# Grove_-_NFC_Tag_v1_0.net
KiCad netlist of a schematic drawn in EAGLE
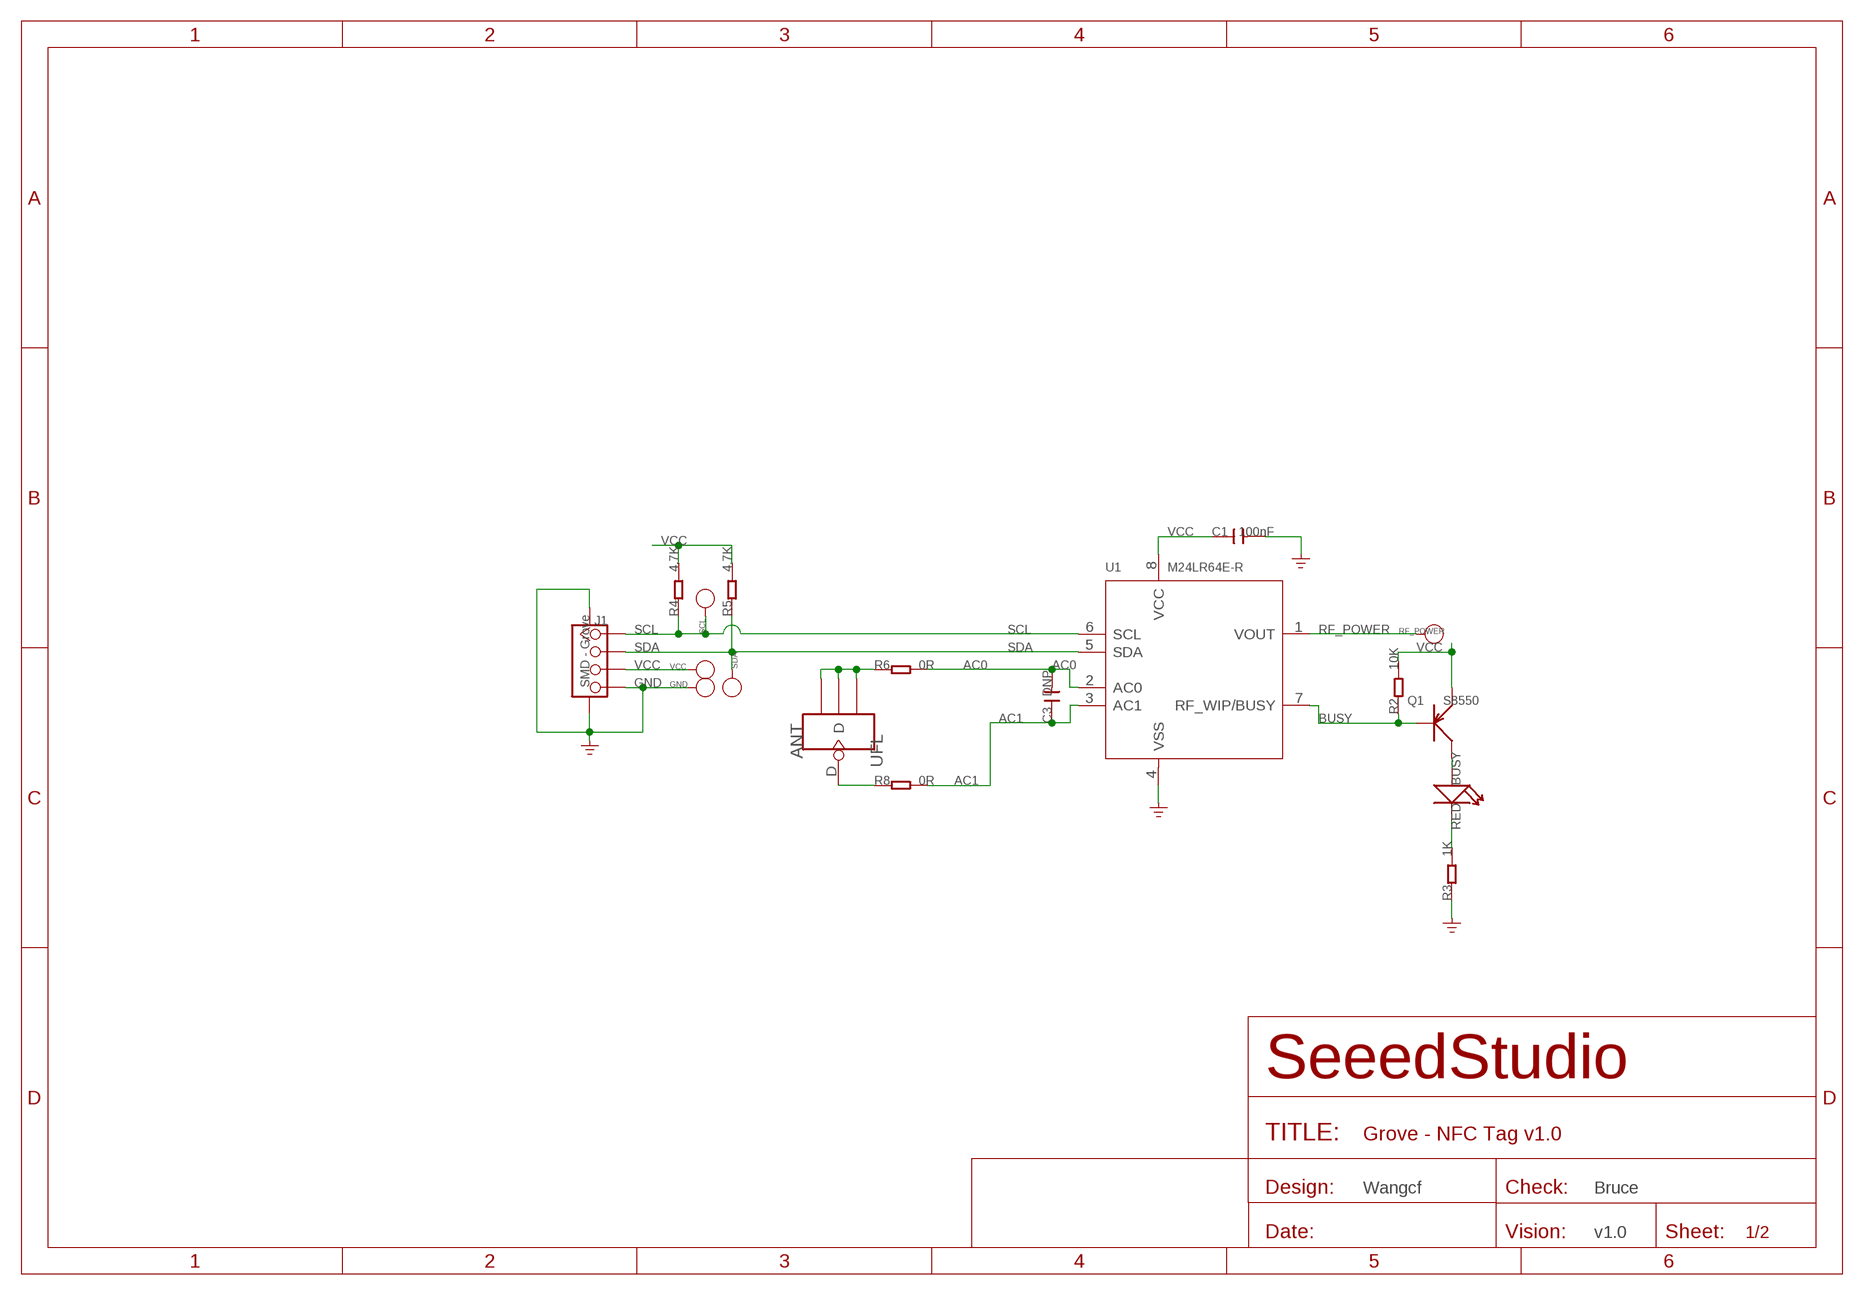
[diagram p0: schematic, sheet 1]
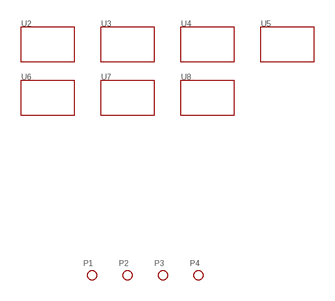
[diagram p1: schematic, sheet 2]

(export (version "E")
  (design (tool "Eeschema 10.0.6"))
  (components
    (comp (ref "ANT")
      (value "UFL")
      (footprint "eagle-import:4P-U-FL")
      (libsource (lib "eagle-import") (part "ANTENNA-U-FL"))
    )
    (comp (ref "BUSY")
      (value "RED")
      (footprint "eagle-import:LED-0603")
      (libsource (lib "eagle-import") (part "LED'0603'"))
    )
    (comp (ref "C1")
      (value "100nF")
      (footprint "eagle-import:C0402")
      (libsource (lib "eagle-import") (part "C-0402"))
    )
    (comp (ref "C3")
      (value "DNP")
      (footprint "eagle-import:C0402")
      (libsource (lib "eagle-import") (part "C-0402"))
    )
    (comp (ref "GND")
      (value "PAD-TEST-POINT'4545'")
      (footprint "eagle-import:TP_4545")
      (fields (field (name "PARTNO") "DNP"))
      (libsource (lib "eagle-import") (part "PAD-TEST-POINT'4545'"))
    )
    (comp (ref "J1")
      (value "SMD - Grove")
      (footprint "eagle-import:4P-SMD-2.0")
      (libsource (lib "eagle-import") (part "TWIG-4P-2.0-SMD-FEMALE-REINFORCE'DD'"))
    )
    (comp (ref "Q1")
      (value "S8550")
      (footprint "eagle-import:SOT23")
      (libsource (lib "eagle-import") (part "TRANSISTOR-PNP-SOT23"))
    )
    (comp (ref "R2")
      (value "10K")
      (footprint "eagle-import:R0402")
      (libsource (lib "eagle-import") (part "R-0402"))
    )
    (comp (ref "R3")
      (value "1K")
      (footprint "eagle-import:R0402")
      (libsource (lib "eagle-import") (part "R-0402"))
    )
    (comp (ref "R4")
      (value "4.7K")
      (footprint "eagle-import:R0402")
      (libsource (lib "eagle-import") (part "R-0402"))
    )
    (comp (ref "R5")
      (value "4.7K")
      (footprint "eagle-import:R0402")
      (libsource (lib "eagle-import") (part "R-0402"))
    )
    (comp (ref "R6")
      (value "0R")
      (footprint "eagle-import:R0402")
      (libsource (lib "eagle-import") (part "R-0402"))
    )
    (comp (ref "R8")
      (value "0R")
      (footprint "eagle-import:R0402")
      (libsource (lib "eagle-import") (part "R-0402"))
    )
    (comp (ref "RF_POWER")
      (value "PAD-TEST-POINT'4545'")
      (footprint "eagle-import:TP_4545")
      (fields (field (name "PARTNO") "DNP"))
      (libsource (lib "eagle-import") (part "PAD-TEST-POINT'4545'"))
    )
    (comp (ref "SCL")
      (value "PAD-TEST-POINT'4545'")
      (footprint "eagle-import:TP_4545")
      (fields (field (name "PARTNO") "DNP"))
      (libsource (lib "eagle-import") (part "PAD-TEST-POINT'4545'"))
    )
    (comp (ref "SDA")
      (value "PAD-TEST-POINT'4545'")
      (footprint "eagle-import:TP_4545")
      (fields (field (name "PARTNO") "DNP"))
      (libsource (lib "eagle-import") (part "PAD-TEST-POINT'4545'"))
    )
    (comp (ref "U1")
      (value "M24LR64E-R")
      (footprint "eagle-import:TSSOP8")
      (libsource (lib "eagle-import") (part "M24LR64E-R"))
    )
    (comp (ref "VCC")
      (value "PAD-TEST-POINT'4545'")
      (footprint "eagle-import:TP_4545")
      (fields (field (name "PARTNO") "DNP"))
      (libsource (lib "eagle-import") (part "PAD-TEST-POINT'4545'"))
    )
    (comp (ref "P1")
      (value "PAD-MARK")
      (footprint "eagle-import:ROUND-MARK-1.0")
      (fields (field (name "PARTNO") "DNP"))
      (libsource (lib "eagle-import") (part "PAD-MARK"))
    )
    (comp (ref "P2")
      (value "PAD-MARK")
      (footprint "eagle-import:ROUND-MARK-1.0")
      (fields (field (name "PARTNO") "DNP"))
      (libsource (lib "eagle-import") (part "PAD-MARK"))
    )
    (comp (ref "P3")
      (value "PAD-MARK")
      (footprint "eagle-import:ROUND-MARK-1.0")
      (fields (field (name "PARTNO") "DNP"))
      (libsource (lib "eagle-import") (part "PAD-MARK"))
    )
    (comp (ref "P4")
      (value "PAD-MARK")
      (footprint "eagle-import:ROUND-MARK-1.0")
      (fields (field (name "PARTNO") "DNP"))
      (libsource (lib "eagle-import") (part "PAD-MARK"))
    )
    (comp (ref "U2")
      (value "TWIG'2U'")
      (footprint "eagle-import:GROVE-TEST-PLATFORM")
      (libsource (lib "eagle-import") (part "TWIG'2U'"))
    )
    (comp (ref "U3")
      (value "TWIG'2U'")
      (footprint "eagle-import:GROVE-TEST-PLATFORM")
      (libsource (lib "eagle-import") (part "TWIG'2U'"))
    )
    (comp (ref "U4")
      (value "TWIG'2U'")
      (footprint "eagle-import:GROVE-TEST-PLATFORM")
      (libsource (lib "eagle-import") (part "TWIG'2U'"))
    )
    (comp (ref "U5")
      (value "TWIG'2U'")
      (footprint "eagle-import:GROVE-TEST-PLATFORM")
      (libsource (lib "eagle-import") (part "TWIG'2U'"))
    )
    (comp (ref "U6")
      (value "TWIG'2U'")
      (footprint "eagle-import:GROVE-TEST-PLATFORM")
      (libsource (lib "eagle-import") (part "TWIG'2U'"))
    )
    (comp (ref "U7")
      (value "TWIG'2U'")
      (footprint "eagle-import:GROVE-TEST-PLATFORM")
      (libsource (lib "eagle-import") (part "TWIG'2U'"))
    )
    (comp (ref "U8")
      (value "TWIG'2U'")
      (footprint "eagle-import:GROVE-TEST-PLATFORM")
      (libsource (lib "eagle-import") (part "TWIG'2U'"))
    )
  )
  (nets
    (net (code "1") (name "AC0") (class "Default")
      (node (ref "C3") (pin "2") (pinfunction "2_2") (pintype "passive"))
      (node (ref "R6") (pin "2") (pinfunction "2_2") (pintype "passive"))
      (node (ref "U1") (pin "2") (pinfunction "AC0_2") (pintype "bidirectional"))
    )
    (net (code "2") (name "AC1") (class "Default")
      (node (ref "C3") (pin "1") (pinfunction "1_1") (pintype "passive"))
      (node (ref "R8") (pin "2") (pinfunction "2_2") (pintype "passive"))
      (node (ref "U1") (pin "3") (pinfunction "AC1_3") (pintype "bidirectional"))
    )
    (net (code "3") (name "BUSY") (class "Default")
      (node (ref "Q1") (pin "1") (pinfunction "B_1") (pintype "passive"))
      (node (ref "R2") (pin "1") (pinfunction "1_1") (pintype "passive"))
      (node (ref "U1") (pin "7") (pinfunction "RF_WIP/BUSY_7") (pintype "bidirectional"))
    )
    (net (code "4") (name "GND") (class "Default")
      (node (ref "C1") (pin "2") (pinfunction "2_2") (pintype "passive"))
      (node (ref "GND") (pin "T") (pinfunction "T_T") (pintype "bidirectional"))
      (node (ref "J1") (pin "4") (pinfunction "4_4") (pintype "bidirectional"))
      (node (ref "J1") (pin "SS1") (pinfunction "SS1_SS1") (pintype "bidirectional"))
      (node (ref "J1") (pin "SS2") (pinfunction "SS2_SS2") (pintype "bidirectional"))
      (node (ref "R3") (pin "1") (pinfunction "1_1") (pintype "passive"))
      (node (ref "U1") (pin "4") (pinfunction "VSS_4") (pintype "bidirectional"))
    )
    (net (code "5") (name "Net-(ANT-PadD)") (class "Default")
      (node (ref "ANT") (pin "D") (pinfunction "D_D") (pintype "bidirectional"))
      (node (ref "R8") (pin "1") (pinfunction "1_1") (pintype "passive"))
    )
    (net (code "6") (name "Net-(ANT-PadGND1)") (class "Default")
      (node (ref "ANT") (pin "GND1") (pinfunction "GND1_GND1") (pintype "bidirectional"))
      (node (ref "ANT") (pin "GND2") (pinfunction "GND2_GND2") (pintype "bidirectional"))
      (node (ref "ANT") (pin "GND3") (pinfunction "GND3_GND3") (pintype "bidirectional"))
      (node (ref "R6") (pin "1") (pinfunction "1_1") (pintype "passive"))
    )
    (net (code "7") (name "Net-(BUSY-Pad-)") (class "Default")
      (node (ref "BUSY") (pin "-") (pinfunction "-_-") (pintype "passive"))
      (node (ref "R3") (pin "2") (pinfunction "2_2") (pintype "passive"))
    )
    (net (code "8") (name "Net-(Q1-C)") (class "Default")
      (node (ref "BUSY") (pin "+") (pinfunction "+_+") (pintype "passive"))
      (node (ref "Q1") (pin "3") (pinfunction "C_3") (pintype "passive"))
    )
    (net (code "9") (name "RF_POWER") (class "Default")
      (node (ref "RF_POWER") (pin "T") (pinfunction "T_T") (pintype "bidirectional"))
      (node (ref "U1") (pin "1") (pinfunction "VOUT_1") (pintype "bidirectional"))
    )
    (net (code "10") (name "SCL") (class "Default")
      (node (ref "J1") (pin "1") (pinfunction "1_1") (pintype "bidirectional"))
      (node (ref "R4") (pin "1") (pinfunction "1_1") (pintype "passive"))
      (node (ref "SCL") (pin "T") (pinfunction "T_T") (pintype "bidirectional"))
      (node (ref "U1") (pin "6") (pinfunction "SCL_6") (pintype "bidirectional"))
    )
    (net (code "11") (name "SDA") (class "Default")
      (node (ref "J1") (pin "2") (pinfunction "2_2") (pintype "bidirectional"))
      (node (ref "R5") (pin "1") (pinfunction "1_1") (pintype "passive"))
      (node (ref "SDA") (pin "T") (pinfunction "T_T") (pintype "bidirectional"))
      (node (ref "U1") (pin "5") (pinfunction "SDA_5") (pintype "bidirectional"))
    )
    (net (code "12") (name "VCC") (class "Default")
      (node (ref "C1") (pin "1") (pinfunction "1_1") (pintype "passive"))
      (node (ref "J1") (pin "3") (pinfunction "3_3") (pintype "bidirectional"))
      (node (ref "Q1") (pin "2") (pinfunction "E_2") (pintype "passive"))
      (node (ref "R2") (pin "2") (pinfunction "2_2") (pintype "passive"))
      (node (ref "R4") (pin "2") (pinfunction "2_2") (pintype "passive"))
      (node (ref "R5") (pin "2") (pinfunction "2_2") (pintype "passive"))
      (node (ref "U1") (pin "8") (pinfunction "VCC_8") (pintype "bidirectional"))
      (node (ref "VCC") (pin "T") (pinfunction "T_T") (pintype "bidirectional"))
    )
  )
)
